# Medusa_9x8_audio.net
KiCad netlist of a schematic drawn in Altium Designer
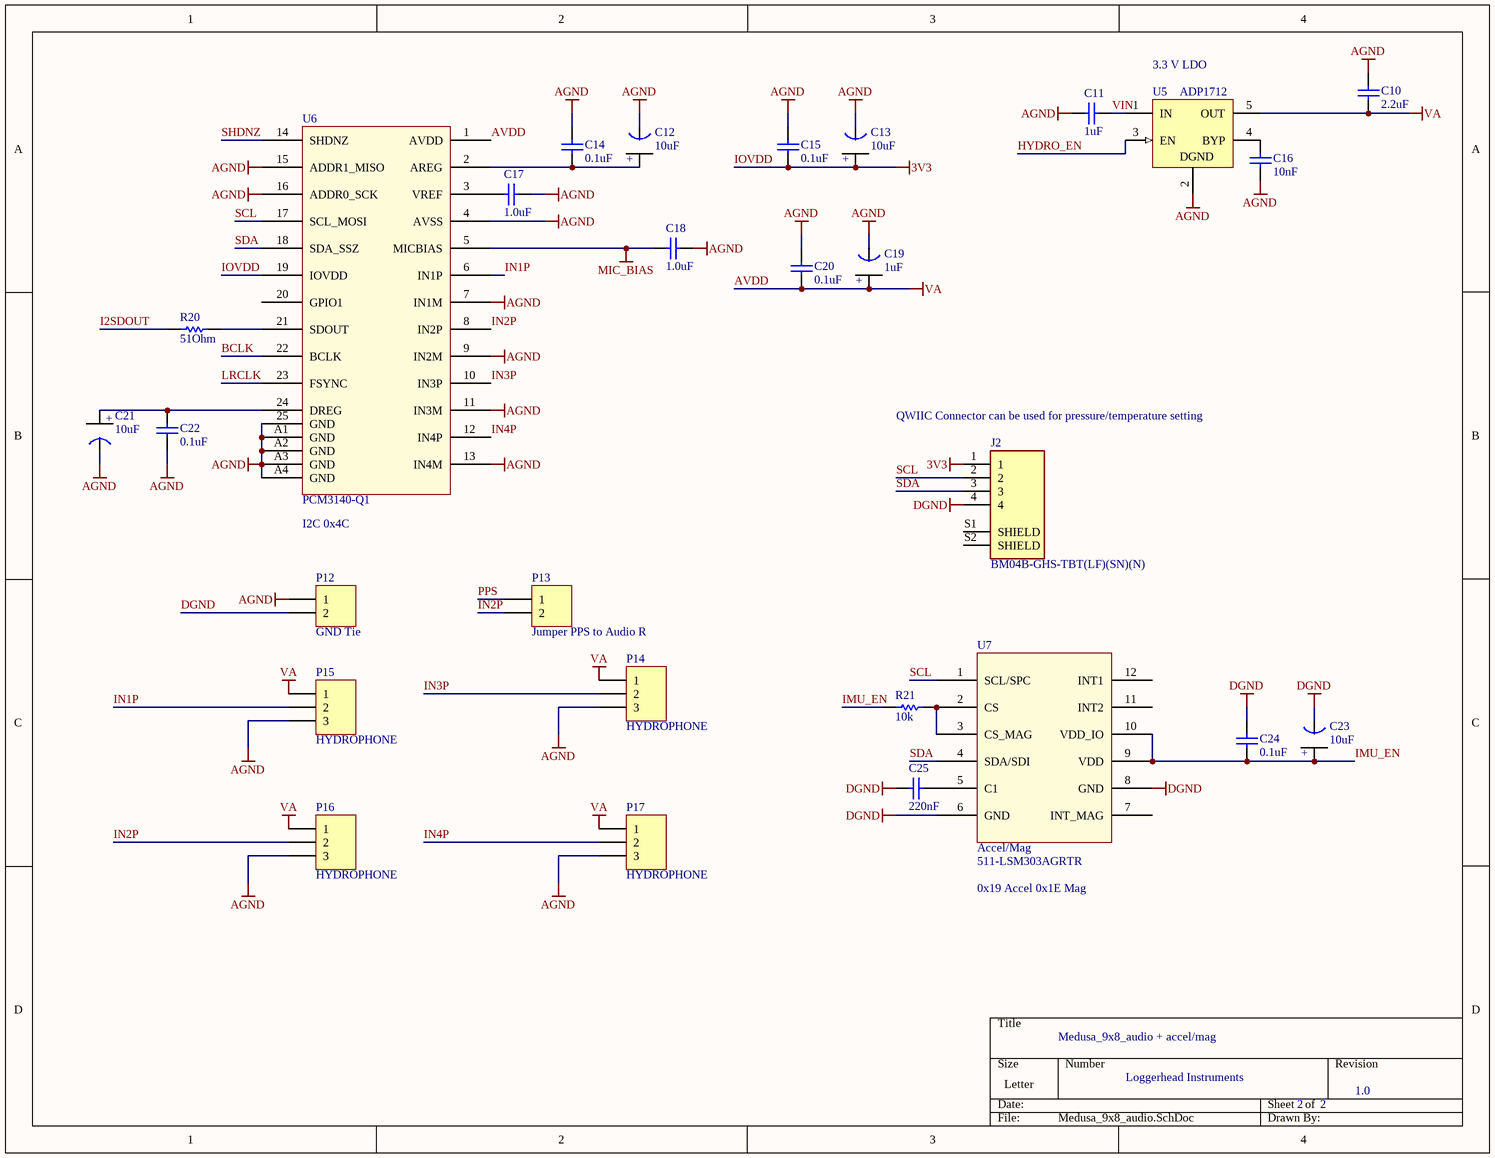
[diagram p0: Medusa_9x8_audio.SchDoc]

(export (version "E")
  (design (tool "Eeschema 10.0.6"))
  (components
    (comp (ref "C10")
      (value "2.2uF")
      (footprint "0402")
      (description "Ceramic Chip Capacitor - Standard")
      (fields (field (name "PUBLISHER") "Altium Limited"))
      (libsource (lib "KEMET Chip Capacitor") (part "C0402"))
    )
    (comp (ref "C11")
      (value "1uF")
      (footprint "0402")
      (description "Ceramic Chip Capacitor - Standard")
      (fields (field (name "PUBLISHER") "Altium Limited"))
      (libsource (lib "KEMET Chip Capacitor") (part "C0402"))
    )
    (comp (ref "C12") (value "10uF") (footprint "Tant0805") (libsource (lib "Loggerhead") (part "Tant0805")))
    (comp (ref "C13") (value "10uF") (footprint "Tant0805") (libsource (lib "Loggerhead") (part "Tant0805")))
    (comp (ref "C14")
      (value "0.1uF")
      (footprint "0402")
      (description "Ceramic Chip Capacitor - Standard")
      (fields (field (name "PUBLISHER") "Altium Limited"))
      (libsource (lib "KEMET Chip Capacitor") (part "C0402"))
    )
    (comp (ref "C15")
      (value "0.1uF")
      (footprint "0402")
      (description "Ceramic Chip Capacitor - Standard")
      (fields (field (name "PUBLISHER") "Altium Limited"))
      (libsource (lib "KEMET Chip Capacitor") (part "C0402"))
    )
    (comp (ref "C16")
      (value "10nF")
      (footprint "0402")
      (description "Ceramic Chip Capacitor - Standard")
      (fields (field (name "PUBLISHER") "Altium Limited"))
      (libsource (lib "KEMET Chip Capacitor") (part "C0402"))
    )
    (comp (ref "C17")
      (value "1.0uF")
      (footprint "0402")
      (description "Ceramic Chip Capacitor - Standard")
      (fields (field (name "PUBLISHER") "Altium Limited"))
      (libsource (lib "KEMET Chip Capacitor") (part "C0402"))
    )
    (comp (ref "C18")
      (value "1.0uF")
      (footprint "0402")
      (description "Ceramic Chip Capacitor - Standard")
      (fields (field (name "PUBLISHER") "Altium Limited"))
      (libsource (lib "KEMET Chip Capacitor") (part "C0402"))
    )
    (comp (ref "C19") (value "1uF") (footprint "Tant0805") (libsource (lib "Loggerhead") (part "Tant0805")))
    (comp (ref "C20")
      (value "0.1uF")
      (footprint "0402")
      (description "Ceramic Chip Capacitor - Standard")
      (fields (field (name "PUBLISHER") "Altium Limited"))
      (libsource (lib "KEMET Chip Capacitor") (part "C0402"))
    )
    (comp (ref "C21") (value "10uF") (footprint "Tant0805") (libsource (lib "Loggerhead") (part "Tant0805")))
    (comp (ref "C22")
      (value "0.1uF")
      (footprint "0402")
      (description "Ceramic Chip Capacitor - Standard")
      (fields (field (name "PUBLISHER") "Altium Limited"))
      (libsource (lib "KEMET Chip Capacitor") (part "C0402"))
    )
    (comp (ref "C23") (value "10uF") (footprint "Tant0805") (libsource (lib "Loggerhead") (part "Tant0805")))
    (comp (ref "C24")
      (value "0.1uF")
      (footprint "0402")
      (description "Ceramic Chip Capacitor - Standard")
      (fields (field (name "PUBLISHER") "Altium Limited"))
      (libsource (lib "KEMET Chip Capacitor") (part "C0402"))
    )
    (comp (ref "C25")
      (value "220nF")
      (footprint "0402")
      (description "Ceramic Chip Capacitor - Standard")
      (fields (field (name "PUBLISHER") "Altium Limited"))
      (libsource (lib "KEMET Chip Capacitor") (part "C0402"))
    )
    (comp (ref "J2")
      (value "BM04B-GHS-TBT(LF)(SN)(N)")
      (footprint "JST_BM04B-GHS-TBT(LF)(SN)(N)")
      (description "Connector Header Surface Mount 4 position 0.049 _1.25mm_")
      (fields (field (name "MF") "JST Sales") (field (name "DIGI-KEY_PART_NUMBER") "455-1580-1-ND"))
      (libsource (lib "BM04B-GHS-TBT_LF__SN__N_") (part "BM04B-GHS-TBT(LF)(SN)(N)"))
    )
    (comp (ref "P12")
      (value "GND Tie")
      (footprint "HDR1X2")
      (description "Header, 2-Pin")
      (fields (field (name "PUBLISHER") "Altium Limited"))
      (libsource (lib "Miscellaneous Connectors") (part "Header 2"))
    )
    (comp (ref "P13")
      (value "Jumper PPS to Audio R")
      (footprint "HDR1X2")
      (description "Header, 2-Pin")
      (fields (field (name "PUBLISHER") "Altium Limited"))
      (libsource (lib "Miscellaneous Connectors") (part "Header 2"))
    )
    (comp (ref "P14")
      (value "HYDROPHONE")
      (footprint "HDR1X3")
      (description "Header, 3-Pin")
      (fields (field (name "PUBLISHER") "Altium Limited"))
      (libsource (lib "Miscellaneous Connectors") (part "Header 3"))
    )
    (comp (ref "P15")
      (value "HYDROPHONE")
      (footprint "HDR1X3")
      (description "Header, 3-Pin")
      (fields (field (name "PUBLISHER") "Altium Limited"))
      (libsource (lib "Miscellaneous Connectors") (part "Header 3"))
    )
    (comp (ref "P16")
      (value "HYDROPHONE")
      (footprint "HDR1X3")
      (description "Header, 3-Pin")
      (fields (field (name "PUBLISHER") "Altium Limited"))
      (libsource (lib "Miscellaneous Connectors") (part "Header 3"))
    )
    (comp (ref "P17")
      (value "HYDROPHONE")
      (footprint "HDR1X3")
      (description "Header, 3-Pin")
      (fields (field (name "PUBLISHER") "Altium Limited"))
      (libsource (lib "Miscellaneous Connectors") (part "Header 3"))
    )
    (comp (ref "R20")
      (value "51Ohm")
      (footprint "2-0402")
      (fields (field (name "PUBLISHER") "Altium Limited"))
      (libsource (lib "Panasonic Resistor") (part "ERJ2RB"))
    )
    (comp (ref "R21")
      (value "10k")
      (footprint "2-0402")
      (fields (field (name "PUBLISHER") "Altium Limited"))
      (libsource (lib "Panasonic Resistor") (part "ERJ2RB"))
    )
    (comp (ref "U5")
      (value "ADP1712")
      (footprint "MF05A_N")
      (description "Micropower, 150mA Low-Noise Ultra Low-Dropout CMOS Voltage Regulator")
      (fields
        (field (name "PARTNUMBER") "LP3985IM5-3.3")
        (field (name "MANUFACTURER") "National Semiconductor")
        (field (name "PUBLISHER") "Altium Limited")
      )
      (libsource (lib "NSC LDO") (part "LP3985IM5-3.3"))
    )
    (comp (ref "U6")
      (value "PCM3140-Q1")
      (footprint "PCM3140")
      (libsource (lib "Loggerhead") (part "PCM3140-Q1"))
    )
    (comp (ref "U7")
      (value "Accel/Mag")
      (footprint "LGA-12")
      (fields (field (name "SUPPLIER PART NUMBER 1") "511-LSM303AGRTR"))
      (libsource (lib "Loggerhead") (part "LSM303AGR"))
    )
  )
  (nets
    (net (code "1") (name "/BCLK") (class "Default")
      (node (ref "U6") (pin "22") (pinfunction "BCLK_22") (pintype "passive"))
    )
    (net (code "2") (name "/HYDRO_EN") (class "Default")
      (node (ref "U5") (pin "3") (pinfunction "EN_3") (pintype "input"))
    )
    (net (code "3") (name "/I2SDOUT") (class "Default")
      (node (ref "R20") (pin "1") (pinfunction "1_1") (pintype "passive"))
    )
    (net (code "4") (name "/IMU_EN") (class "Default")
      (node (ref "C23") (pin "2") (pinfunction "+_2") (pintype "passive"))
      (node (ref "C24") (pin "1") (pinfunction "1_1") (pintype "passive"))
      (node (ref "R21") (pin "2") (pinfunction "2_2") (pintype "passive"))
      (node (ref "U7") (pin "10") (pinfunction "VDD_IO_10") (pintype "passive"))
      (node (ref "U7") (pin "9") (pinfunction "VDD_9") (pintype "passive"))
    )
    (net (code "5") (name "/IN1P") (class "Default")
      (node (ref "P15") (pin "2") (pinfunction "2_2") (pintype "passive"))
      (node (ref "U6") (pin "6") (pinfunction "IN1P_6") (pintype "passive"))
    )
    (net (code "6") (name "/IN2P") (class "Default")
      (node (ref "P13") (pin "2") (pinfunction "2_2") (pintype "passive"))
      (node (ref "P16") (pin "2") (pinfunction "2_2") (pintype "passive"))
      (node (ref "U6") (pin "8") (pinfunction "IN2P_8") (pintype "passive"))
    )
    (net (code "7") (name "/IN3P") (class "Default")
      (node (ref "P14") (pin "2") (pinfunction "2_2") (pintype "passive"))
      (node (ref "U6") (pin "10") (pinfunction "IN3P_10") (pintype "passive"))
    )
    (net (code "8") (name "/IN4P") (class "Default")
      (node (ref "P17") (pin "2") (pinfunction "2_2") (pintype "passive"))
      (node (ref "U6") (pin "12") (pinfunction "IN4P_12") (pintype "passive"))
    )
    (net (code "9") (name "/LRCLK") (class "Default")
      (node (ref "U6") (pin "23") (pinfunction "FSYNC_23") (pintype "passive"))
    )
    (net (code "10") (name "/PPS") (class "Default")
      (node (ref "P13") (pin "1") (pinfunction "1_1") (pintype "passive"))
    )
    (net (code "11") (name "/SCL") (class "Default")
      (node (ref "J2") (pin "2") (pinfunction "2_2") (pintype "passive"))
      (node (ref "U6") (pin "17") (pinfunction "SCL_MOSI_17") (pintype "passive"))
      (node (ref "U7") (pin "1") (pinfunction "SCL/SPC_1") (pintype "passive"))
    )
    (net (code "12") (name "/SDA") (class "Default")
      (node (ref "J2") (pin "3") (pinfunction "3_3") (pintype "passive"))
      (node (ref "U6") (pin "18") (pinfunction "SDA_SSZ_18") (pintype "passive"))
      (node (ref "U7") (pin "4") (pinfunction "SDA/SDI_4") (pintype "passive"))
    )
    (net (code "13") (name "/SHDNZ") (class "Default")
      (node (ref "U6") (pin "14") (pinfunction "SHDNZ_14") (pintype "passive"))
    )
    (net (code "14") (name "/VIN") (class "Default")
      (node (ref "C11") (pin "1") (pinfunction "1_1") (pintype "passive"))
      (node (ref "U5") (pin "1") (pinfunction "IN_1") (pintype "power_in"))
    )
    (net (code "15") (name "3V3") (class "Default")
      (node (ref "C13") (pin "2") (pinfunction "+_2") (pintype "passive"))
      (node (ref "C15") (pin "2") (pinfunction "2_2") (pintype "passive"))
      (node (ref "J2") (pin "1") (pinfunction "1_1") (pintype "passive"))
      (node (ref "U6") (pin "19") (pinfunction "IOVDD_19") (pintype "passive"))
    )
    (net (code "16") (name "AGND") (class "Default")
      (node (ref "C10") (pin "2") (pinfunction "2_2") (pintype "passive"))
      (node (ref "C11") (pin "2") (pinfunction "2_2") (pintype "passive"))
      (node (ref "C12") (pin "1") (pinfunction "GND_1") (pintype "passive"))
      (node (ref "C13") (pin "1") (pinfunction "GND_1") (pintype "passive"))
      (node (ref "C14") (pin "1") (pinfunction "1_1") (pintype "passive"))
      (node (ref "C15") (pin "1") (pinfunction "1_1") (pintype "passive"))
      (node (ref "C16") (pin "2") (pinfunction "2_2") (pintype "passive"))
      (node (ref "C17") (pin "1") (pinfunction "1_1") (pintype "passive"))
      (node (ref "C18") (pin "1") (pinfunction "1_1") (pintype "passive"))
      (node (ref "C19") (pin "1") (pinfunction "GND_1") (pintype "passive"))
      (node (ref "C20") (pin "1") (pinfunction "1_1") (pintype "passive"))
      (node (ref "C21") (pin "1") (pinfunction "GND_1") (pintype "passive"))
      (node (ref "C22") (pin "1") (pinfunction "1_1") (pintype "passive"))
      (node (ref "P12") (pin "1") (pinfunction "1_1") (pintype "passive"))
      (node (ref "P14") (pin "3") (pinfunction "3_3") (pintype "passive"))
      (node (ref "P15") (pin "3") (pinfunction "3_3") (pintype "passive"))
      (node (ref "P16") (pin "3") (pinfunction "3_3") (pintype "passive"))
      (node (ref "P17") (pin "3") (pinfunction "3_3") (pintype "passive"))
      (node (ref "U5") (pin "2") (pinfunction "GND_2") (pintype "power_in"))
      (node (ref "U6") (pin "11") (pinfunction "IN3M_11") (pintype "passive"))
      (node (ref "U6") (pin "13") (pinfunction "IN4M_13") (pintype "passive"))
      (node (ref "U6") (pin "15") (pinfunction "ADDR1_MISO_15") (pintype "passive"))
      (node (ref "U6") (pin "16") (pinfunction "ADDR0_SCK_16") (pintype "passive"))
      (node (ref "U6") (pin "25") (pinfunction "GND_25") (pintype "passive"))
      (node (ref "U6") (pin "4") (pinfunction "AVSS_4") (pintype "passive"))
      (node (ref "U6") (pin "7") (pinfunction "IN1M_7") (pintype "passive"))
      (node (ref "U6") (pin "9") (pinfunction "IN2M_9") (pintype "passive"))
      (node (ref "U6") (pin "A1") (pinfunction "GND_A1") (pintype "passive"))
      (node (ref "U6") (pin "A2") (pinfunction "GND_A2") (pintype "passive"))
      (node (ref "U6") (pin "A3") (pinfunction "GND_A3") (pintype "passive"))
      (node (ref "U6") (pin "A4") (pinfunction "GND_A4") (pintype "passive"))
    )
    (net (code "17") (name "DGND") (class "Default")
      (node (ref "C23") (pin "1") (pinfunction "GND_1") (pintype "passive"))
      (node (ref "C24") (pin "2") (pinfunction "2_2") (pintype "passive"))
      (node (ref "C25") (pin "1") (pinfunction "1_1") (pintype "passive"))
      (node (ref "J2") (pin "4") (pinfunction "4_4") (pintype "passive"))
      (node (ref "P12") (pin "2") (pinfunction "2_2") (pintype "passive"))
      (node (ref "U7") (pin "6") (pinfunction "GND_6") (pintype "passive"))
      (node (ref "U7") (pin "8") (pinfunction "GND_8") (pintype "passive"))
    )
    (net (code "18") (name "MIC_BIAS") (class "Default")
      (node (ref "C18") (pin "2") (pinfunction "2_2") (pintype "passive"))
      (node (ref "U6") (pin "5") (pinfunction "MICBIAS_5") (pintype "passive"))
    )
    (net (code "19") (name "Net-(C12-+)") (class "Default")
      (node (ref "C12") (pin "2") (pinfunction "+_2") (pintype "passive"))
      (node (ref "C14") (pin "2") (pinfunction "2_2") (pintype "passive"))
      (node (ref "U6") (pin "2") (pinfunction "AREG_2") (pintype "passive"))
    )
    (net (code "20") (name "Net-(C21-+)") (class "Default")
      (node (ref "C21") (pin "2") (pinfunction "+_2") (pintype "passive"))
      (node (ref "C22") (pin "2") (pinfunction "2_2") (pintype "passive"))
      (node (ref "U6") (pin "24") (pinfunction "DREG_24") (pintype "passive"))
    )
    (net (code "21") (name "Net-(U5-BYP)") (class "Default")
      (node (ref "C16") (pin "1") (pinfunction "1_1") (pintype "passive"))
      (node (ref "U5") (pin "4") (pinfunction "BYP_4") (pintype "passive"))
    )
    (net (code "22") (name "Net-(U6-SDOUT)") (class "Default")
      (node (ref "R20") (pin "2") (pinfunction "2_2") (pintype "passive"))
      (node (ref "U6") (pin "21") (pinfunction "SDOUT_21") (pintype "passive"))
    )
    (net (code "23") (name "Net-(U6-VREF)") (class "Default")
      (node (ref "C17") (pin "2") (pinfunction "2_2") (pintype "passive"))
      (node (ref "U6") (pin "3") (pinfunction "VREF_3") (pintype "passive"))
    )
    (net (code "24") (name "Net-(U7-C1)") (class "Default")
      (node (ref "C25") (pin "2") (pinfunction "2_2") (pintype "passive"))
      (node (ref "U7") (pin "5") (pinfunction "C1_5") (pintype "passive"))
    )
    (net (code "25") (name "Net-(U7-CS)") (class "Default")
      (node (ref "R21") (pin "1") (pinfunction "1_1") (pintype "passive"))
      (node (ref "U7") (pin "2") (pinfunction "CS_2") (pintype "passive"))
      (node (ref "U7") (pin "3") (pinfunction "CS_MAG_3") (pintype "passive"))
    )
    (net (code "26") (name "VA") (class "Default")
      (node (ref "C10") (pin "1") (pinfunction "1_1") (pintype "passive"))
      (node (ref "C19") (pin "2") (pinfunction "+_2") (pintype "passive"))
      (node (ref "C20") (pin "2") (pinfunction "2_2") (pintype "passive"))
      (node (ref "P14") (pin "1") (pinfunction "1_1") (pintype "passive"))
      (node (ref "P15") (pin "1") (pinfunction "1_1") (pintype "passive"))
      (node (ref "P16") (pin "1") (pinfunction "1_1") (pintype "passive"))
      (node (ref "P17") (pin "1") (pinfunction "1_1") (pintype "passive"))
      (node (ref "U5") (pin "5") (pinfunction "OUT_5") (pintype "power_in"))
      (node (ref "U6") (pin "1") (pinfunction "AVDD_1") (pintype "passive"))
    )
    (net (code "27") (name "unconnected-(J2-SHIELD-PadS1)") (class "Default")
      (node (ref "J2") (pin "S1") (pinfunction "SHIELD_S1") (pintype "passive"))
    )
    (net (code "28") (name "unconnected-(J2-SHIELD-PadS2)") (class "Default")
      (node (ref "J2") (pin "S2") (pinfunction "SHIELD_S2") (pintype "passive"))
    )
    (net (code "29") (name "unconnected-(U6-GPIO1-Pad20)") (class "Default")
      (node (ref "U6") (pin "20") (pinfunction "GPIO1_20") (pintype "passive"))
    )
    (net (code "30") (name "unconnected-(U7-INT1-Pad12)") (class "Default")
      (node (ref "U7") (pin "12") (pinfunction "INT1_12") (pintype "passive"))
    )
    (net (code "31") (name "unconnected-(U7-INT2-Pad11)") (class "Default")
      (node (ref "U7") (pin "11") (pinfunction "INT2_11") (pintype "passive"))
    )
    (net (code "32") (name "unconnected-(U7-INT_MAG-Pad7)") (class "Default")
      (node (ref "U7") (pin "7") (pinfunction "INT_MAG_7") (pintype "passive"))
    )
  )
)
